# MAX86141_HEG_MINI_HEADPIECE.net
KiCad netlist of a schematic drawn in EAGLE
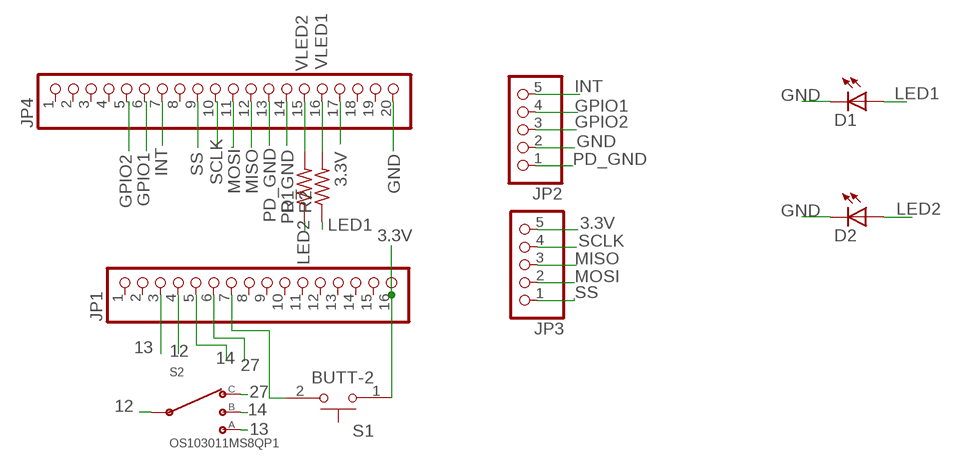
[diagram p0: schematic, sheet 1]

(export (version "E")
  (design (tool "Eeschema 10.0.6"))
  (components
    (comp (ref "D1")
      (value "LED1206")
      (footprint "eagle-import:LED-1206")
      (libsource (lib "eagle-import") (part "LED1206"))
    )
    (comp (ref "D2")
      (value "LED1206")
      (footprint "eagle-import:LED-1206")
      (libsource (lib "eagle-import") (part "LED1206"))
    )
    (comp (ref "JP1")
      (value "PINHD-1X16")
      (footprint "eagle-import:1X16")
      (libsource (lib "eagle-import") (part "PINHD-1X16"))
    )
    (comp (ref "JP2")
      (value "PINHD-1X5")
      (footprint "eagle-import:1X05")
      (libsource (lib "eagle-import") (part "PINHD-1X5"))
    )
    (comp (ref "JP3")
      (value "PINHD-1X5")
      (footprint "eagle-import:1X05")
      (libsource (lib "eagle-import") (part "PINHD-1X5"))
    )
    (comp (ref "JP4")
      (value "PINHD-1X20")
      (footprint "eagle-import:1X20")
      (libsource (lib "eagle-import") (part "PINHD-1X20"))
    )
    (comp (ref "R1")
      (value "R-US_0204/5")
      (footprint "eagle-import:0204_5")
      (libsource (lib "eagle-import") (part "R-US_0204/5"))
    )
    (comp (ref "R2")
      (value "R-US_0204/5")
      (footprint "eagle-import:0204_5")
      (libsource (lib "eagle-import") (part "R-US_0204/5"))
    )
    (comp (ref "S1")
      (value "BUTT-2")
      (footprint "eagle-import:SW_BUTT-2")
      (fields (field (name "MF") "Gravitech"))
      (libsource (lib "eagle-import") (part "BUTT-2"))
    )
    (comp (ref "S2")
      (value "OS103011MS8QP1")
      (footprint "eagle-import:OS102011MS8QP1")
      (fields (field (name "MF") "C&K"))
      (libsource (lib "eagle-import") (part "OS103011MS8QP1"))
    )
  )
  (nets
    (net (code "1") (name "/3.3V") (class "Default")
      (node (ref "JP1") (pin "16") (pinfunction "16_16") (pintype "passive"))
      (node (ref "JP3") (pin "5") (pinfunction "5_5") (pintype "passive"))
      (node (ref "JP4") (pin "17") (pinfunction "17_17") (pintype "passive"))
      (node (ref "S1") (pin "1") (pinfunction "1_1") (pintype "passive"))
    )
    (net (code "2") (name "/12") (class "Default")
      (node (ref "JP1") (pin "4") (pinfunction "4_4") (pintype "passive"))
      (node (ref "S2") (pin "2") (pinfunction "C_2") (pintype "bidirectional"))
    )
    (net (code "3") (name "/13") (class "Default")
      (node (ref "JP1") (pin "3") (pinfunction "3_3") (pintype "passive"))
      (node (ref "S2") (pin "1") (pinfunction "1_1") (pintype "bidirectional"))
    )
    (net (code "4") (name "/14") (class "Default")
      (node (ref "JP1") (pin "5") (pinfunction "5_5") (pintype "passive"))
      (node (ref "S2") (pin "3") (pinfunction "2_3") (pintype "bidirectional"))
    )
    (net (code "5") (name "/27") (class "Default")
      (node (ref "JP1") (pin "6") (pinfunction "6_6") (pintype "passive"))
      (node (ref "S2") (pin "4") (pinfunction "3_4") (pintype "bidirectional"))
    )
    (net (code "6") (name "/GND") (class "Default")
      (node (ref "D1") (pin "C") (pinfunction "C_C") (pintype "passive"))
      (node (ref "D2") (pin "C") (pinfunction "C_C") (pintype "passive"))
      (node (ref "JP2") (pin "2") (pinfunction "2_2") (pintype "passive"))
      (node (ref "JP4") (pin "20") (pinfunction "20_20") (pintype "passive"))
    )
    (net (code "7") (name "/GPIO1") (class "Default")
      (node (ref "JP2") (pin "4") (pinfunction "4_4") (pintype "passive"))
      (node (ref "JP4") (pin "6") (pinfunction "6_6") (pintype "passive"))
    )
    (net (code "8") (name "/GPIO2") (class "Default")
      (node (ref "JP2") (pin "3") (pinfunction "3_3") (pintype "passive"))
      (node (ref "JP4") (pin "5") (pinfunction "5_5") (pintype "passive"))
    )
    (net (code "9") (name "/INT") (class "Default")
      (node (ref "JP2") (pin "5") (pinfunction "5_5") (pintype "passive"))
      (node (ref "JP4") (pin "7") (pinfunction "7_7") (pintype "passive"))
    )
    (net (code "10") (name "/LED1") (class "Default")
      (node (ref "D1") (pin "A") (pinfunction "A_A") (pintype "passive"))
      (node (ref "R2") (pin "1") (pinfunction "1_1") (pintype "passive"))
    )
    (net (code "11") (name "/LED2") (class "Default")
      (node (ref "D2") (pin "A") (pinfunction "A_A") (pintype "passive"))
      (node (ref "R1") (pin "1") (pinfunction "1_1") (pintype "passive"))
    )
    (net (code "12") (name "/MISO") (class "Default")
      (node (ref "JP3") (pin "3") (pinfunction "3_3") (pintype "passive"))
      (node (ref "JP4") (pin "12") (pinfunction "12_12") (pintype "passive"))
    )
    (net (code "13") (name "/MOSI") (class "Default")
      (node (ref "JP3") (pin "2") (pinfunction "2_2") (pintype "passive"))
      (node (ref "JP4") (pin "11") (pinfunction "11_11") (pintype "passive"))
    )
    (net (code "14") (name "/PD_GND") (class "Default")
      (node (ref "JP2") (pin "1") (pinfunction "1_1") (pintype "passive"))
      (node (ref "JP4") (pin "13") (pinfunction "13_13") (pintype "passive"))
      (node (ref "JP4") (pin "14") (pinfunction "14_14") (pintype "passive"))
    )
    (net (code "15") (name "/SCLK") (class "Default")
      (node (ref "JP3") (pin "4") (pinfunction "4_4") (pintype "passive"))
      (node (ref "JP4") (pin "10") (pinfunction "10_10") (pintype "passive"))
    )
    (net (code "16") (name "/SS") (class "Default")
      (node (ref "JP3") (pin "1") (pinfunction "1_1") (pintype "passive"))
      (node (ref "JP4") (pin "9") (pinfunction "9_9") (pintype "passive"))
    )
    (net (code "17") (name "/VLED1") (class "Default")
      (node (ref "JP4") (pin "16") (pinfunction "16_16") (pintype "passive"))
      (node (ref "R2") (pin "2") (pinfunction "2_2") (pintype "passive"))
    )
    (net (code "18") (name "/VLED2") (class "Default")
      (node (ref "JP4") (pin "15") (pinfunction "15_15") (pintype "passive"))
      (node (ref "R1") (pin "2") (pinfunction "2_2") (pintype "passive"))
    )
    (net (code "19") (name "Net-(JP1-Pad7)") (class "Default")
      (node (ref "JP1") (pin "7") (pinfunction "7_7") (pintype "passive"))
      (node (ref "S1") (pin "2") (pinfunction "2_2") (pintype "passive"))
    )
    (net (code "20") (name "unconnected-(JP1-Pad1)") (class "Default")
      (node (ref "JP1") (pin "1") (pinfunction "1_1") (pintype "passive"))
    )
    (net (code "21") (name "unconnected-(JP1-Pad2)") (class "Default")
      (node (ref "JP1") (pin "2") (pinfunction "2_2") (pintype "passive"))
    )
    (net (code "22") (name "unconnected-(JP1-Pad8)") (class "Default")
      (node (ref "JP1") (pin "8") (pinfunction "8_8") (pintype "passive"))
    )
    (net (code "23") (name "unconnected-(JP1-Pad9)") (class "Default")
      (node (ref "JP1") (pin "9") (pinfunction "9_9") (pintype "passive"))
    )
    (net (code "24") (name "unconnected-(JP1-Pad10)") (class "Default")
      (node (ref "JP1") (pin "10") (pinfunction "10_10") (pintype "passive"))
    )
    (net (code "25") (name "unconnected-(JP1-Pad11)") (class "Default")
      (node (ref "JP1") (pin "11") (pinfunction "11_11") (pintype "passive"))
    )
    (net (code "26") (name "unconnected-(JP1-Pad12)") (class "Default")
      (node (ref "JP1") (pin "12") (pinfunction "12_12") (pintype "passive"))
    )
    (net (code "27") (name "unconnected-(JP1-Pad13)") (class "Default")
      (node (ref "JP1") (pin "13") (pinfunction "13_13") (pintype "passive"))
    )
    (net (code "28") (name "unconnected-(JP1-Pad14)") (class "Default")
      (node (ref "JP1") (pin "14") (pinfunction "14_14") (pintype "passive"))
    )
    (net (code "29") (name "unconnected-(JP1-Pad15)") (class "Default")
      (node (ref "JP1") (pin "15") (pinfunction "15_15") (pintype "passive"))
    )
    (net (code "30") (name "unconnected-(JP4-Pad1)") (class "Default")
      (node (ref "JP4") (pin "1") (pinfunction "1_1") (pintype "passive"))
    )
    (net (code "31") (name "unconnected-(JP4-Pad2)") (class "Default")
      (node (ref "JP4") (pin "2") (pinfunction "2_2") (pintype "passive"))
    )
    (net (code "32") (name "unconnected-(JP4-Pad3)") (class "Default")
      (node (ref "JP4") (pin "3") (pinfunction "3_3") (pintype "passive"))
    )
    (net (code "33") (name "unconnected-(JP4-Pad4)") (class "Default")
      (node (ref "JP4") (pin "4") (pinfunction "4_4") (pintype "passive"))
    )
    (net (code "34") (name "unconnected-(JP4-Pad8)") (class "Default")
      (node (ref "JP4") (pin "8") (pinfunction "8_8") (pintype "passive"))
    )
    (net (code "35") (name "unconnected-(JP4-Pad18)") (class "Default")
      (node (ref "JP4") (pin "18") (pinfunction "18_18") (pintype "passive"))
    )
    (net (code "36") (name "unconnected-(JP4-Pad19)") (class "Default")
      (node (ref "JP4") (pin "19") (pinfunction "19_19") (pintype "passive"))
    )
  )
)
